# Power.net
KiCad netlist of a schematic drawn in Altium Designer
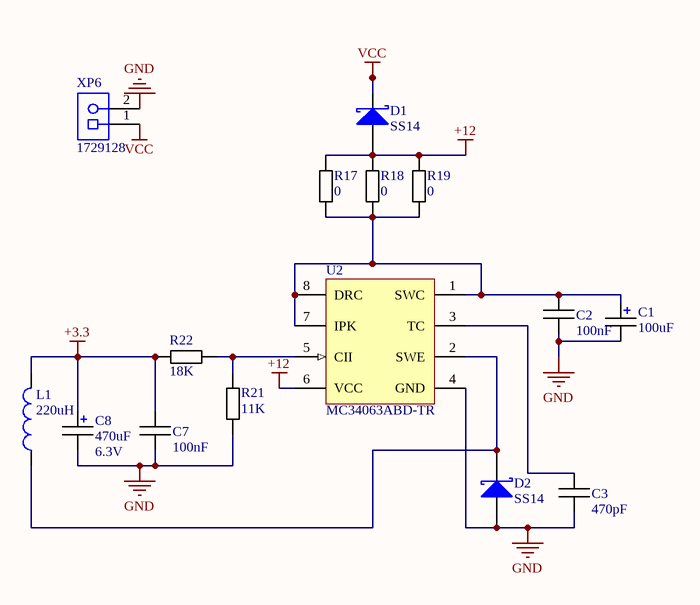
[diagram p0: Power.SchDoc]

(export (version "E")
  (design (tool "Eeschema 10.0.6"))
  (components
    (comp (ref "C1")
      (value "CAP_ELEC_SMD")
      (footprint "ECAP_SMD_6.3mmx5.4mm")
      (fields (field (name "VAL") "100uF"))
      (libsource (lib "altium-import") (part "root_3_CAP_ELEC_SMD_"))
    )
    (comp (ref "C2")
      (value "CAP_SMD")
      (footprint "CAPC1206(3216)170_L")
      (description "Ceramic capacitor, 0805")
      (fields (field (name "VAL") "100nF"))
      (libsource (lib "altium-import") (part "root_1_CAP_SMD_"))
    )
    (comp (ref "C3")
      (value "CAP_SMD")
      (footprint "CAPC1206(3216)170_L")
      (description "Ceramic capacitor, 0805")
      (fields (field (name "VAL") "470pF"))
      (libsource (lib "altium-import") (part "root_1_CAP_SMD_"))
    )
    (comp (ref "C7")
      (value "CAP_SMD")
      (footprint "CAPC1206(3216)170_L")
      (description "Ceramic capacitor, 0805")
      (fields (field (name "VAL") "100nF"))
      (libsource (lib "altium-import") (part "root_1_CAP_SMD_"))
    )
    (comp (ref "C8")
      (value "CAP_ELEC_SMD")
      (footprint "ECAP_SMD_8mmx10mm")
      (fields (field (name "RATED CAPACITANCE") "470uF") (field (name "RATED VOLTAGE") "6.3V"))
      (libsource (lib "altium-import") (part "root_3_CAP_ELEC_SMD_"))
    )
    (comp (ref "D1")
      (value "SS14")
      (footprint "DO-214")
      (description "Schottky Rectifier, 1.1 W, -65 to 125 degC, 2-Pin SMD, RoHS, Tape and Reel")
      (fields (field (name "MANUFACTURER") "Fairchild"))
      (libsource (lib "altium-import") (part "root_1_SS14_"))
    )
    (comp (ref "D2")
      (value "SS14")
      (footprint "DO-214")
      (description "Schottky Rectifier, 1.1 W, -65 to 125 degC, 2-Pin SMD, RoHS, Tape and Reel")
      (fields (field (name "MANUFACTURER") "Fairchild"))
      (libsource (lib "altium-import") (part "root_1_SS14_"))
    )
    (comp (ref "L1")
      (value "220uH")
      (footprint "SDR1006_SMD")
      (description "Inductor for Power Circuits")
      (fields (field (name "TOLERANCE") "±30%") (field (name "MANUFACTURER") "TDK"))
      (libsource (lib "web.skorpio") (part "Inductor power"))
    )
    (comp (ref "R17")
      (value "RES_SMD")
      (footprint "RESC1206(3216)_L")
      (description "RES0805")
      (fields (field (name "VAL") "0"))
      (libsource (lib "altium-import") (part "root_1_RES_SMD_"))
    )
    (comp (ref "R18")
      (value "RES_SMD")
      (footprint "RESC1206(3216)_L")
      (description "RES0805")
      (fields (field (name "VAL") "0"))
      (libsource (lib "altium-import") (part "root_1_RES_SMD_"))
    )
    (comp (ref "R19")
      (value "RES_SMD")
      (footprint "RESC1206(3216)_L")
      (description "RES0805")
      (fields (field (name "VAL") "0"))
      (libsource (lib "altium-import") (part "root_1_RES_SMD_"))
    )
    (comp (ref "R21")
      (value "RES_SMD")
      (footprint "RESC1206(3216)_L")
      (description "RES0805")
      (fields (field (name "VAL") "11K"))
      (libsource (lib "altium-import") (part "root_3_RES_SMD_"))
    )
    (comp (ref "R22")
      (value "RES_SMD")
      (footprint "RESC1206(3216)_L")
      (description "RES0805")
      (fields (field (name "VAL") "18K"))
      (libsource (lib "altium-import") (part "root_2_RES_SMD_"))
    )
    (comp (ref "U2")
      (value "MC34063ABD-TR")
      (footprint "SO-8_M")
      (description "DC/DC converter control circuit, 8-Pin SO, Tape and Reel")
      (libsource (lib "altium-import") (part "root_0_MC34063A_"))
    )
    (comp (ref "XP6")
      (value "1729128")
      (footprint "PHOE-1729128-2_V")
      (description "PCB Terminal Block, 13.5 A, 400 V, 2-Pin THD, RoHS, Bulk")
      (fields (field (name "MANUFACTURER") "Phoenix Contact"))
      (libsource (lib "altium-import") (part "root_2_Terminal_2_Green_"))
    )
  )
  (nets
    (net (code "1") (name "+3.3") (class "Default")
      (node (ref "C7") (pin "2") (pinfunction "2_2") (pintype "passive"))
      (node (ref "C8") (pin "1") (pinfunction "1_1") (pintype "passive"))
      (node (ref "L1") (pin "2") (pinfunction "2_2") (pintype "passive"))
      (node (ref "R22") (pin "2") (pinfunction "2_2") (pintype "passive"))
    )
    (net (code "2") (name "+12") (class "Default")
      (node (ref "D1") (pin "2") (pinfunction "A_2") (pintype "passive"))
      (node (ref "R17") (pin "2") (pinfunction "2_2") (pintype "passive"))
      (node (ref "R18") (pin "2") (pinfunction "2_2") (pintype "passive"))
      (node (ref "R19") (pin "2") (pinfunction "2_2") (pintype "passive"))
      (node (ref "U2") (pin "6") (pinfunction "VCC_6") (pintype "power_in"))
    )
    (net (code "3") (name "GND") (class "Default")
      (node (ref "C1") (pin "2") (pinfunction "2_2") (pintype "passive"))
      (node (ref "C2") (pin "1") (pinfunction "1_1") (pintype "passive"))
      (node (ref "C3") (pin "1") (pinfunction "1_1") (pintype "passive"))
      (node (ref "C7") (pin "1") (pinfunction "1_1") (pintype "passive"))
      (node (ref "C8") (pin "2") (pinfunction "2_2") (pintype "passive"))
      (node (ref "D2") (pin "2") (pinfunction "A_2") (pintype "passive"))
      (node (ref "R21") (pin "2") (pinfunction "2_2") (pintype "passive"))
      (node (ref "U2") (pin "4") (pinfunction "GND_4") (pintype "power_in"))
      (node (ref "XP6") (pin "2") (pinfunction "2_2") (pintype "passive"))
    )
    (net (code "4") (name "Net-(D2-K)") (class "Default")
      (node (ref "D2") (pin "1") (pinfunction "K_1") (pintype "passive"))
      (node (ref "L1") (pin "1") (pinfunction "1_1") (pintype "passive"))
      (node (ref "U2") (pin "2") (pinfunction "SWE_2") (pintype "open_emitter"))
    )
    (net (code "5") (name "Net-(U2-CII)") (class "Default")
      (node (ref "R21") (pin "1") (pinfunction "1_1") (pintype "passive"))
      (node (ref "R22") (pin "1") (pinfunction "1_1") (pintype "passive"))
      (node (ref "U2") (pin "5") (pinfunction "CII_5") (pintype "input"))
    )
    (net (code "6") (name "Net-(U2-DRC)") (class "Default")
      (node (ref "C1") (pin "1") (pinfunction "1_1") (pintype "passive"))
      (node (ref "C2") (pin "2") (pinfunction "2_2") (pintype "passive"))
      (node (ref "R17") (pin "1") (pinfunction "1_1") (pintype "passive"))
      (node (ref "R18") (pin "1") (pinfunction "1_1") (pintype "passive"))
      (node (ref "R19") (pin "1") (pinfunction "1_1") (pintype "passive"))
      (node (ref "U2") (pin "1") (pinfunction "SWC_1") (pintype "open_collector"))
      (node (ref "U2") (pin "7") (pinfunction "IPK_7") (pintype "passive"))
      (node (ref "U2") (pin "8") (pinfunction "DRC_8") (pintype "open_collector"))
    )
    (net (code "7") (name "Net-(U2-TC)") (class "Default")
      (node (ref "C3") (pin "2") (pinfunction "2_2") (pintype "passive"))
      (node (ref "U2") (pin "3") (pinfunction "TC_3") (pintype "passive"))
    )
    (net (code "8") (name "VCC") (class "Default")
      (node (ref "D1") (pin "1") (pinfunction "K_1") (pintype "passive"))
      (node (ref "XP6") (pin "1") (pinfunction "1_1") (pintype "passive"))
    )
  )
)
